# bareduino-V1R3.net
KiCad netlist of a schematic drawn in EAGLE
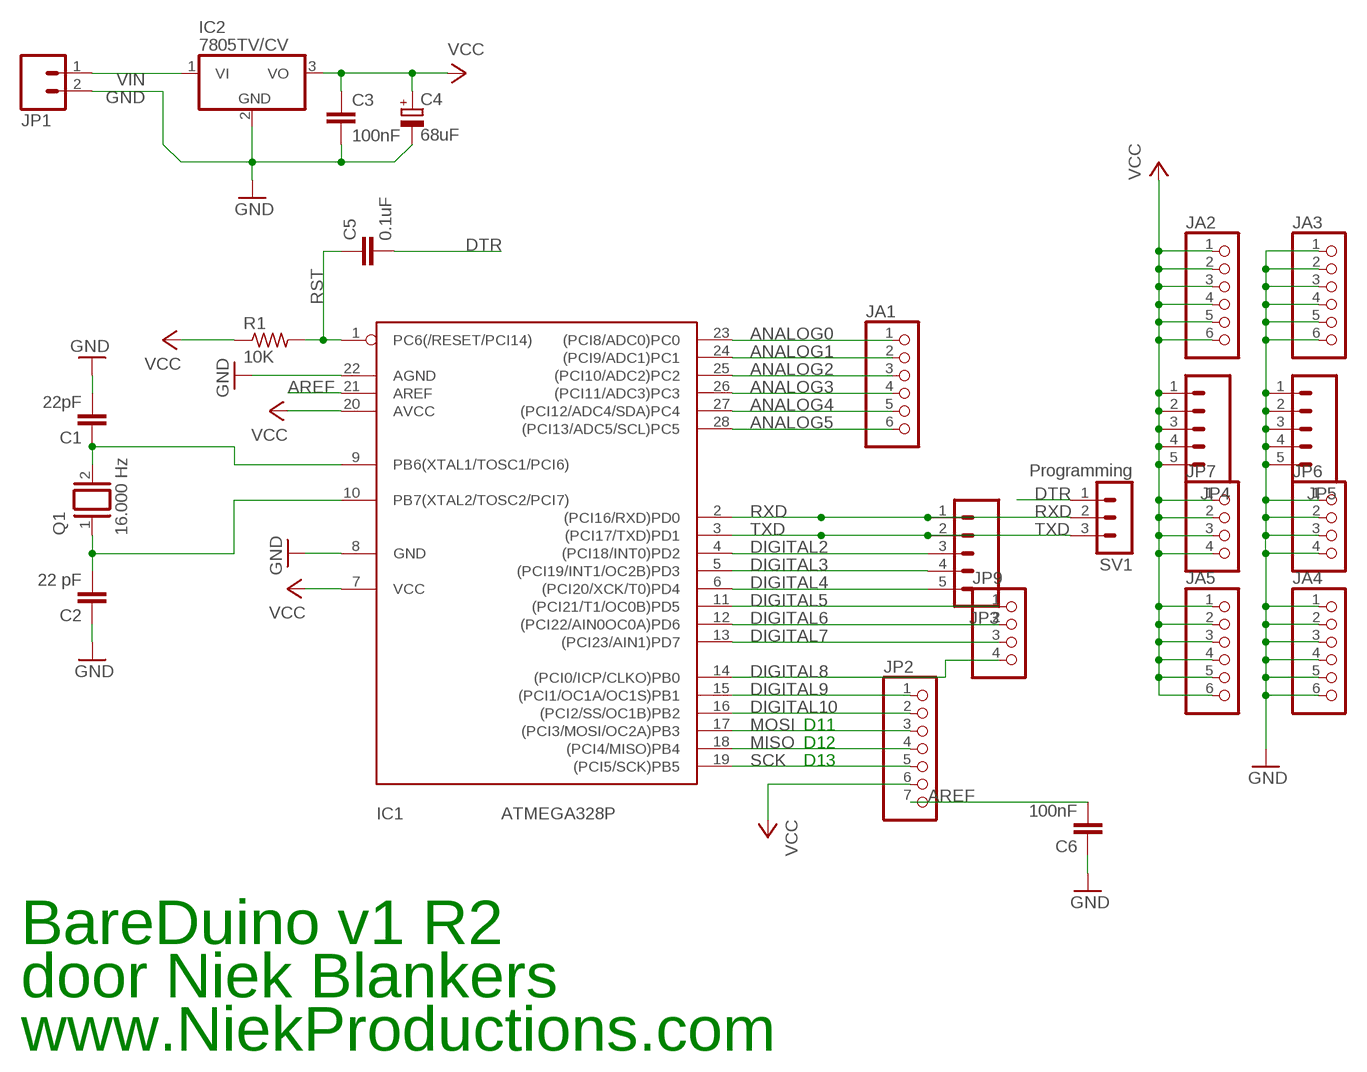
[diagram p0: schematic, sheet 1]

(export (version "E")
  (design (tool "Eeschema 10.0.6"))
  (components
    (comp (ref "C1")
      (value "22pF")
      (footprint "eagle-import:C025-024X044")
      (libsource (lib "eagle-import") (part "C-EU025-024X044"))
    )
    (comp (ref "C2")
      (value "22 pF")
      (footprint "eagle-import:C025-024X044")
      (libsource (lib "eagle-import") (part "C-EU025-024X044"))
    )
    (comp (ref "C3")
      (value "100nF")
      (footprint "eagle-import:C025-025X050")
      (libsource (lib "eagle-import") (part "C-EU025-025X050"))
    )
    (comp (ref "C4")
      (value "68uF")
      (footprint "eagle-import:E2,5-6E")
      (libsource (lib "eagle-import") (part "CPOL-EUE2,5-6E"))
    )
    (comp (ref "C5")
      (value "0.1uF")
      (footprint "eagle-import:C025-024X044")
      (libsource (lib "eagle-import") (part "C-EU025-024X044"))
    )
    (comp (ref "C6")
      (value "100nF")
      (footprint "eagle-import:C025-024X044")
      (libsource (lib "eagle-import") (part "C-EU025-024X044"))
    )
    (comp (ref "IC1")
      (value "ATMEGA328P")
      (footprint "eagle-import:DIL28_3")
      (libsource (lib "eagle-import") (part "ATMEGA168PROUND"))
    )
    (comp (ref "IC2")
      (value "7805TV/CV")
      (footprint "eagle-import:TO220V")
      (libsource (lib "eagle-import") (part "78TV05"))
    )
    (comp (ref "JA1")
      (value "PINHD-1X6CB")
      (footprint "eagle-import:1X06-CLEANBIG")
      (libsource (lib "eagle-import") (part "PINHD-1X6CB"))
    )
    (comp (ref "JA2")
      (value "PINHD-1X6CB")
      (footprint "eagle-import:1X06-CLEANBIG")
      (libsource (lib "eagle-import") (part "PINHD-1X6CB"))
    )
    (comp (ref "JA3")
      (value "PINHD-1X6CB")
      (footprint "eagle-import:1X06-CLEANBIG")
      (libsource (lib "eagle-import") (part "PINHD-1X6CB"))
    )
    (comp (ref "JA4")
      (value "PINHD-1X6CB")
      (footprint "eagle-import:1X06-CLEANBIG")
      (libsource (lib "eagle-import") (part "PINHD-1X6CB"))
    )
    (comp (ref "JA5")
      (value "PINHD-1X6CB")
      (footprint "eagle-import:1X06-CLEANBIG")
      (libsource (lib "eagle-import") (part "PINHD-1X6CB"))
    )
    (comp (ref "JP1")
      (value "M025MM")
      (footprint "eagle-import:SCREWTERMINAL-5MM-2")
      (libsource (lib "eagle-import") (part "M025MM"))
    )
    (comp (ref "JP2")
      (value "PINHD-1X07_2.54-S")
      (footprint "eagle-import:1X07-S")
      (libsource (lib "eagle-import") (part "PINHD-1X07_2.54-S"))
    )
    (comp (ref "JP3")
      (value "M05PTH")
      (footprint "eagle-import:1X05")
      (libsource (lib "eagle-import") (part "M05PTH"))
    )
    (comp (ref "JP4")
      (value "M05PTH")
      (footprint "eagle-import:1X05")
      (libsource (lib "eagle-import") (part "M05PTH"))
    )
    (comp (ref "JP5")
      (value "M05PTH")
      (footprint "eagle-import:1X05")
      (libsource (lib "eagle-import") (part "M05PTH"))
    )
    (comp (ref "JP6")
      (value "PINHD-1X04_2.54-S")
      (footprint "eagle-import:1X04-S")
      (libsource (lib "eagle-import") (part "PINHD-1X04_2.54-S"))
    )
    (comp (ref "JP7")
      (value "PINHD-1X04_2.54-S")
      (footprint "eagle-import:1X04-S")
      (libsource (lib "eagle-import") (part "PINHD-1X04_2.54-S"))
    )
    (comp (ref "JP9")
      (value "PINHD-1X04_2.54-S")
      (footprint "eagle-import:1X04-S")
      (libsource (lib "eagle-import") (part "PINHD-1X04_2.54-S"))
    )
    (comp (ref "Q1")
      (value "16.000 Hz")
      (footprint "eagle-import:QS")
      (libsource (lib "eagle-import") (part "XTAL/S"))
    )
    (comp (ref "R1")
      (value "10K")
      (footprint "eagle-import:0207_5V")
      (libsource (lib "eagle-import") (part "R-US_0207/5V"))
    )
    (comp (ref "SV1")
      (value "Programming")
      (footprint "eagle-import:MA03-1")
      (libsource (lib "eagle-import") (part "MA03-1"))
    )
  )
  (nets
    (net (code "1") (name "/ANALOG0") (class "Default")
      (node (ref "IC1") (pin "23") (pinfunction "(PCI8/ADC0)PC0_23") (pintype "bidirectional"))
      (node (ref "JA1") (pin "1") (pinfunction "1_1") (pintype "passive"))
    )
    (net (code "2") (name "/ANALOG1") (class "Default")
      (node (ref "IC1") (pin "24") (pinfunction "(PCI9/ADC1)PC1_24") (pintype "bidirectional"))
      (node (ref "JA1") (pin "2") (pinfunction "2_2") (pintype "passive"))
    )
    (net (code "3") (name "/ANALOG2") (class "Default")
      (node (ref "IC1") (pin "25") (pinfunction "(PCI10/ADC2)PC2_25") (pintype "bidirectional"))
      (node (ref "JA1") (pin "3") (pinfunction "3_3") (pintype "passive"))
    )
    (net (code "4") (name "/ANALOG3") (class "Default")
      (node (ref "IC1") (pin "26") (pinfunction "(PCI11/ADC3)PC3_26") (pintype "bidirectional"))
      (node (ref "JA1") (pin "4") (pinfunction "4_4") (pintype "passive"))
    )
    (net (code "5") (name "/ANALOG4") (class "Default")
      (node (ref "IC1") (pin "27") (pinfunction "(PCI12/ADC4/SDA)PC4_27") (pintype "bidirectional"))
      (node (ref "JA1") (pin "5") (pinfunction "5_5") (pintype "passive"))
    )
    (net (code "6") (name "/ANALOG5") (class "Default")
      (node (ref "IC1") (pin "28") (pinfunction "(PCI13/ADC5/SCL)PC5_28") (pintype "bidirectional"))
      (node (ref "JA1") (pin "6") (pinfunction "6_6") (pintype "passive"))
    )
    (net (code "7") (name "/AREF") (class "Default")
      (node (ref "C6") (pin "2") (pinfunction "2_2") (pintype "passive"))
      (node (ref "IC1") (pin "21") (pinfunction "AREF_21") (pintype "bidirectional"))
      (node (ref "JP2") (pin "7") (pinfunction "7_7") (pintype "passive"))
    )
    (net (code "8") (name "/DIGITAL2") (class "Default")
      (node (ref "IC1") (pin "4") (pinfunction "(PCI18/INT0)PD2_4") (pintype "bidirectional"))
      (node (ref "JP3") (pin "3") (pinfunction "3_3") (pintype "passive"))
    )
    (net (code "9") (name "/DIGITAL3") (class "Default")
      (node (ref "IC1") (pin "5") (pinfunction "(PCI19/INT1/OC2B)PD3_5") (pintype "bidirectional"))
      (node (ref "JP3") (pin "4") (pinfunction "4_4") (pintype "passive"))
    )
    (net (code "10") (name "/DIGITAL4") (class "Default")
      (node (ref "IC1") (pin "6") (pinfunction "(PCI20/XCK/T0)PD4_6") (pintype "bidirectional"))
      (node (ref "JP3") (pin "5") (pinfunction "5_5") (pintype "passive"))
    )
    (net (code "11") (name "/DIGITAL5") (class "Default")
      (node (ref "IC1") (pin "11") (pinfunction "(PCI21/T1/OC0B)PD5_11") (pintype "bidirectional"))
      (node (ref "JP9") (pin "1") (pinfunction "1_1") (pintype "passive"))
    )
    (net (code "12") (name "/DIGITAL6") (class "Default")
      (node (ref "IC1") (pin "12") (pinfunction "(PCI22/AIN0OC0A)PD6_12") (pintype "bidirectional"))
      (node (ref "JP9") (pin "2") (pinfunction "2_2") (pintype "passive"))
    )
    (net (code "13") (name "/DIGITAL7") (class "Default")
      (node (ref "IC1") (pin "13") (pinfunction "(PCI23/AIN1)PD7_13") (pintype "bidirectional"))
      (node (ref "JP9") (pin "3") (pinfunction "3_3") (pintype "passive"))
    )
    (net (code "14") (name "/DIGITAL8") (class "Default")
      (node (ref "IC1") (pin "14") (pinfunction "(PCI0/ICP/CLKO)PB0_14") (pintype "bidirectional"))
      (node (ref "JP9") (pin "4") (pinfunction "4_4") (pintype "passive"))
    )
    (net (code "15") (name "/DIGITAL9") (class "Default")
      (node (ref "IC1") (pin "15") (pinfunction "(PCI1/OC1A/OC1S)PB1_15") (pintype "bidirectional"))
      (node (ref "JP2") (pin "1") (pinfunction "1_1") (pintype "passive"))
    )
    (net (code "16") (name "/DIGITAL10") (class "Default")
      (node (ref "IC1") (pin "16") (pinfunction "(PCI2/SS/OC1B)PB2_16") (pintype "bidirectional"))
      (node (ref "JP2") (pin "2") (pinfunction "2_2") (pintype "passive"))
    )
    (net (code "17") (name "/DTR") (class "Default")
      (node (ref "C5") (pin "2") (pinfunction "2_2") (pintype "passive"))
      (node (ref "SV1") (pin "1") (pinfunction "1_1") (pintype "passive"))
    )
    (net (code "18") (name "/MISO") (class "Default")
      (node (ref "IC1") (pin "18") (pinfunction "(PCI4/MISO)PB4_18") (pintype "bidirectional"))
      (node (ref "JP2") (pin "4") (pinfunction "4_4") (pintype "passive"))
    )
    (net (code "19") (name "/MOSI") (class "Default")
      (node (ref "IC1") (pin "17") (pinfunction "(PCI3/MOSI/OC2A)PB3_17") (pintype "bidirectional"))
      (node (ref "JP2") (pin "3") (pinfunction "3_3") (pintype "passive"))
    )
    (net (code "20") (name "/RST") (class "Default")
      (node (ref "C5") (pin "1") (pinfunction "1_1") (pintype "passive"))
      (node (ref "IC1") (pin "1") (pinfunction "PC6(/RESET/PCI14)_1") (pintype "bidirectional"))
      (node (ref "R1") (pin "2") (pinfunction "2_2") (pintype "passive"))
    )
    (net (code "21") (name "/RXD") (class "Default")
      (node (ref "IC1") (pin "2") (pinfunction "(PCI16/RXD)PD0_2") (pintype "bidirectional"))
      (node (ref "JP3") (pin "1") (pinfunction "1_1") (pintype "passive"))
      (node (ref "SV1") (pin "2") (pinfunction "2_2") (pintype "passive"))
    )
    (net (code "22") (name "/SCK") (class "Default")
      (node (ref "IC1") (pin "19") (pinfunction "(PCI5/SCK)PB5_19") (pintype "bidirectional"))
      (node (ref "JP2") (pin "5") (pinfunction "5_5") (pintype "passive"))
    )
    (net (code "23") (name "/TXD") (class "Default")
      (node (ref "IC1") (pin "3") (pinfunction "(PCI17/TXD)PD1_3") (pintype "bidirectional"))
      (node (ref "JP3") (pin "2") (pinfunction "2_2") (pintype "passive"))
      (node (ref "SV1") (pin "3") (pinfunction "3_3") (pintype "passive"))
    )
    (net (code "24") (name "/VIN") (class "Default")
      (node (ref "IC2") (pin "1") (pinfunction "VI_1") (pintype "input"))
      (node (ref "JP1") (pin "1") (pinfunction "1_1") (pintype "passive"))
    )
    (net (code "25") (name "GND") (class "Default")
      (node (ref "C1") (pin "2") (pinfunction "2_2") (pintype "passive"))
      (node (ref "C2") (pin "1") (pinfunction "1_1") (pintype "passive"))
      (node (ref "C3") (pin "2") (pinfunction "2_2") (pintype "passive"))
      (node (ref "C4") (pin "-") (pinfunction "-_-") (pintype "passive"))
      (node (ref "C6") (pin "1") (pinfunction "1_1") (pintype "passive"))
      (node (ref "IC1") (pin "22") (pinfunction "AGND_22") (pintype "bidirectional"))
      (node (ref "IC1") (pin "8") (pinfunction "GND_8") (pintype "bidirectional"))
      (node (ref "IC2") (pin "2") (pinfunction "GND_2") (pintype "passive"))
      (node (ref "JA3") (pin "1") (pinfunction "1_1") (pintype "passive"))
      (node (ref "JA3") (pin "2") (pinfunction "2_2") (pintype "passive"))
      (node (ref "JA3") (pin "3") (pinfunction "3_3") (pintype "passive"))
      (node (ref "JA3") (pin "4") (pinfunction "4_4") (pintype "passive"))
      (node (ref "JA3") (pin "5") (pinfunction "5_5") (pintype "passive"))
      (node (ref "JA3") (pin "6") (pinfunction "6_6") (pintype "passive"))
      (node (ref "JA4") (pin "1") (pinfunction "1_1") (pintype "passive"))
      (node (ref "JA4") (pin "2") (pinfunction "2_2") (pintype "passive"))
      (node (ref "JA4") (pin "3") (pinfunction "3_3") (pintype "passive"))
      (node (ref "JA4") (pin "4") (pinfunction "4_4") (pintype "passive"))
      (node (ref "JA4") (pin "5") (pinfunction "5_5") (pintype "passive"))
      (node (ref "JA4") (pin "6") (pinfunction "6_6") (pintype "passive"))
      (node (ref "JP1") (pin "2") (pinfunction "2_2") (pintype "passive"))
      (node (ref "JP5") (pin "1") (pinfunction "1_1") (pintype "passive"))
      (node (ref "JP5") (pin "2") (pinfunction "2_2") (pintype "passive"))
      (node (ref "JP5") (pin "3") (pinfunction "3_3") (pintype "passive"))
      (node (ref "JP5") (pin "4") (pinfunction "4_4") (pintype "passive"))
      (node (ref "JP5") (pin "5") (pinfunction "5_5") (pintype "passive"))
      (node (ref "JP6") (pin "1") (pinfunction "1_1") (pintype "passive"))
      (node (ref "JP6") (pin "2") (pinfunction "2_2") (pintype "passive"))
      (node (ref "JP6") (pin "3") (pinfunction "3_3") (pintype "passive"))
      (node (ref "JP6") (pin "4") (pinfunction "4_4") (pintype "passive"))
    )
    (net (code "26") (name "Net-(IC1-PB6(XTAL1{slash}TOSC1{slash}PCI6))") (class "Default")
      (node (ref "C1") (pin "1") (pinfunction "1_1") (pintype "passive"))
      (node (ref "IC1") (pin "9") (pinfunction "PB6(XTAL1/TOSC1/PCI6)_9") (pintype "bidirectional"))
      (node (ref "Q1") (pin "2") (pinfunction "2_2") (pintype "passive"))
    )
    (net (code "27") (name "Net-(IC1-PB7(XTAL2{slash}TOSC2{slash}PCI7))") (class "Default")
      (node (ref "C2") (pin "2") (pinfunction "2_2") (pintype "passive"))
      (node (ref "IC1") (pin "10") (pinfunction "PB7(XTAL2/TOSC2/PCI7)_10") (pintype "bidirectional"))
      (node (ref "Q1") (pin "1") (pinfunction "1_1") (pintype "passive"))
    )
    (net (code "28") (name "VCC") (class "Default")
      (node (ref "C3") (pin "1") (pinfunction "1_1") (pintype "passive"))
      (node (ref "C4") (pin "+") (pinfunction "+_+") (pintype "passive"))
      (node (ref "IC1") (pin "20") (pinfunction "AVCC_20") (pintype "bidirectional"))
      (node (ref "IC1") (pin "7") (pinfunction "VCC_7") (pintype "bidirectional"))
      (node (ref "IC2") (pin "3") (pinfunction "VO_3") (pintype "passive"))
      (node (ref "JA2") (pin "1") (pinfunction "1_1") (pintype "passive"))
      (node (ref "JA2") (pin "2") (pinfunction "2_2") (pintype "passive"))
      (node (ref "JA2") (pin "3") (pinfunction "3_3") (pintype "passive"))
      (node (ref "JA2") (pin "4") (pinfunction "4_4") (pintype "passive"))
      (node (ref "JA2") (pin "5") (pinfunction "5_5") (pintype "passive"))
      (node (ref "JA2") (pin "6") (pinfunction "6_6") (pintype "passive"))
      (node (ref "JA5") (pin "1") (pinfunction "1_1") (pintype "passive"))
      (node (ref "JA5") (pin "2") (pinfunction "2_2") (pintype "passive"))
      (node (ref "JA5") (pin "3") (pinfunction "3_3") (pintype "passive"))
      (node (ref "JA5") (pin "4") (pinfunction "4_4") (pintype "passive"))
      (node (ref "JA5") (pin "5") (pinfunction "5_5") (pintype "passive"))
      (node (ref "JA5") (pin "6") (pinfunction "6_6") (pintype "passive"))
      (node (ref "JP2") (pin "6") (pinfunction "6_6") (pintype "passive"))
      (node (ref "JP4") (pin "1") (pinfunction "1_1") (pintype "passive"))
      (node (ref "JP4") (pin "2") (pinfunction "2_2") (pintype "passive"))
      (node (ref "JP4") (pin "3") (pinfunction "3_3") (pintype "passive"))
      (node (ref "JP4") (pin "4") (pinfunction "4_4") (pintype "passive"))
      (node (ref "JP4") (pin "5") (pinfunction "5_5") (pintype "passive"))
      (node (ref "JP7") (pin "1") (pinfunction "1_1") (pintype "passive"))
      (node (ref "JP7") (pin "2") (pinfunction "2_2") (pintype "passive"))
      (node (ref "JP7") (pin "3") (pinfunction "3_3") (pintype "passive"))
      (node (ref "JP7") (pin "4") (pinfunction "4_4") (pintype "passive"))
      (node (ref "R1") (pin "1") (pinfunction "1_1") (pintype "passive"))
    )
  )
)
